# blinkycircuitpcb.net
KiCad netlist of a schematic drawn in EAGLE
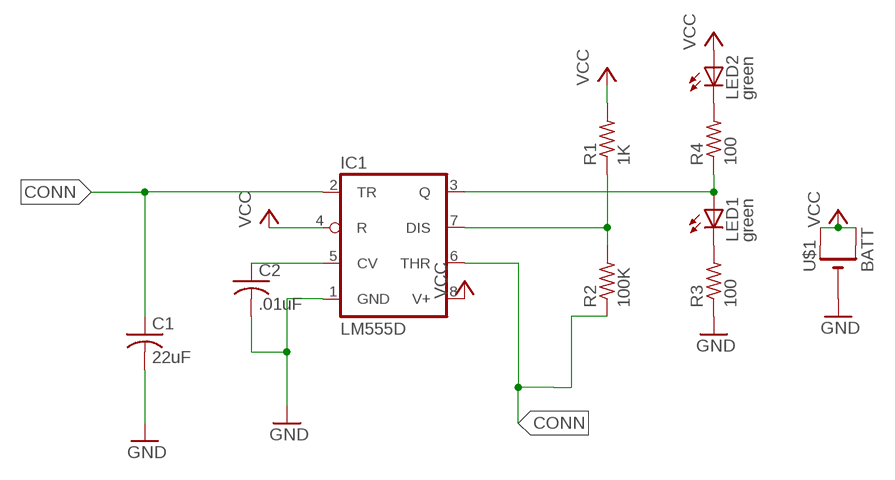
[diagram p0: schematic, sheet 1]

(export (version "E")
  (design (tool "Eeschema 10.0.6"))
  (components
    (comp (ref "C1")
      (value "22uF")
      (footprint "eagle-import:C0805K")
      (libsource (lib "eagle-import") (part "C-USC0805K"))
    )
    (comp (ref "C2")
      (value ".01uF")
      (footprint "eagle-import:C0805K")
      (libsource (lib "eagle-import") (part "C-USC0805K"))
    )
    (comp (ref "IC1")
      (value "LM555D")
      (footprint "eagle-import:SO08")
      (libsource (lib "eagle-import") (part "555DLM"))
    )
    (comp (ref "LED1")
      (value "green")
      (footprint "eagle-import:CHIPLED_0805")
      (libsource (lib "eagle-import") (part "LEDCHIPLED_0805"))
    )
    (comp (ref "LED2")
      (value "green")
      (footprint "eagle-import:CHIPLED_0805")
      (libsource (lib "eagle-import") (part "LEDCHIPLED_0805"))
    )
    (comp (ref "R1")
      (value "1K")
      (footprint "eagle-import:R0805")
      (libsource (lib "eagle-import") (part "R-US_R0805"))
    )
    (comp (ref "R2")
      (value "100K")
      (footprint "eagle-import:R0805")
      (libsource (lib "eagle-import") (part "R-US_R0805"))
    )
    (comp (ref "R3")
      (value "100")
      (footprint "eagle-import:R0805")
      (libsource (lib "eagle-import") (part "R-US_R0805"))
    )
    (comp (ref "R4")
      (value "100")
      (footprint "eagle-import:R0805")
      (libsource (lib "eagle-import") (part "R-US_R0805"))
    )
    (comp (ref "U$1")
      (value "BATT")
      (footprint "eagle-import:CR1220-SMD")
      (libsource (lib "eagle-import") (part "CR1220SMT"))
    )
  )
  (nets
    (net (code "1") (name "CONN") (class "Default")
      (node (ref "C1") (pin "1") (pinfunction "1_1") (pintype "passive"))
      (node (ref "IC1") (pin "2") (pinfunction "TR_2") (pintype "input"))
      (node (ref "IC1") (pin "6") (pinfunction "THR_6") (pintype "input"))
      (node (ref "R2") (pin "1") (pinfunction "1_1") (pintype "passive"))
    )
    (net (code "2") (name "GND") (class "Default")
      (node (ref "C1") (pin "2") (pinfunction "2_2") (pintype "passive"))
      (node (ref "C2") (pin "2") (pinfunction "2_2") (pintype "passive"))
      (node (ref "IC1") (pin "1") (pinfunction "GND_1") (pintype "power_in"))
      (node (ref "R3") (pin "1") (pinfunction "1_1") (pintype "passive"))
      (node (ref "U$1") (pin "-") (pinfunction "-_-") (pintype "passive"))
    )
    (net (code "3") (name "Net-(IC1-CV)") (class "Default")
      (node (ref "C2") (pin "1") (pinfunction "1_1") (pintype "passive"))
      (node (ref "IC1") (pin "5") (pinfunction "CV_5") (pintype "input"))
    )
    (net (code "4") (name "Net-(IC1-DIS)") (class "Default")
      (node (ref "IC1") (pin "7") (pinfunction "DIS_7") (pintype "input"))
      (node (ref "R1") (pin "1") (pinfunction "1_1") (pintype "passive"))
      (node (ref "R2") (pin "2") (pinfunction "2_2") (pintype "passive"))
    )
    (net (code "5") (name "Net-(IC1-Q)") (class "Default")
      (node (ref "IC1") (pin "3") (pinfunction "Q_3") (pintype "output"))
      (node (ref "LED1") (pin "A") (pinfunction "A_A") (pintype "passive"))
      (node (ref "R4") (pin "1") (pinfunction "1_1") (pintype "passive"))
    )
    (net (code "6") (name "Net-(LED1-PadC)") (class "Default")
      (node (ref "LED1") (pin "C") (pinfunction "C_C") (pintype "passive"))
      (node (ref "R3") (pin "2") (pinfunction "2_2") (pintype "passive"))
    )
    (net (code "7") (name "Net-(LED2-PadC)") (class "Default")
      (node (ref "LED2") (pin "C") (pinfunction "C_C") (pintype "passive"))
      (node (ref "R4") (pin "2") (pinfunction "2_2") (pintype "passive"))
    )
    (net (code "8") (name "VCC") (class "Default")
      (node (ref "IC1") (pin "4") (pinfunction "R_4") (pintype "input"))
      (node (ref "IC1") (pin "8") (pinfunction "V+_8") (pintype "power_in"))
      (node (ref "LED2") (pin "A") (pinfunction "A_A") (pintype "passive"))
      (node (ref "R1") (pin "2") (pinfunction "2_2") (pintype "passive"))
      (node (ref "U$1") (pin "+$1") (pinfunction "+_+$1") (pintype "passive"))
      (node (ref "U$1") (pin "+$2") (pinfunction "+1_+$2") (pintype "passive"))
    )
  )
)
